# LCD.net
KiCad netlist of a schematic drawn in Altium Designer
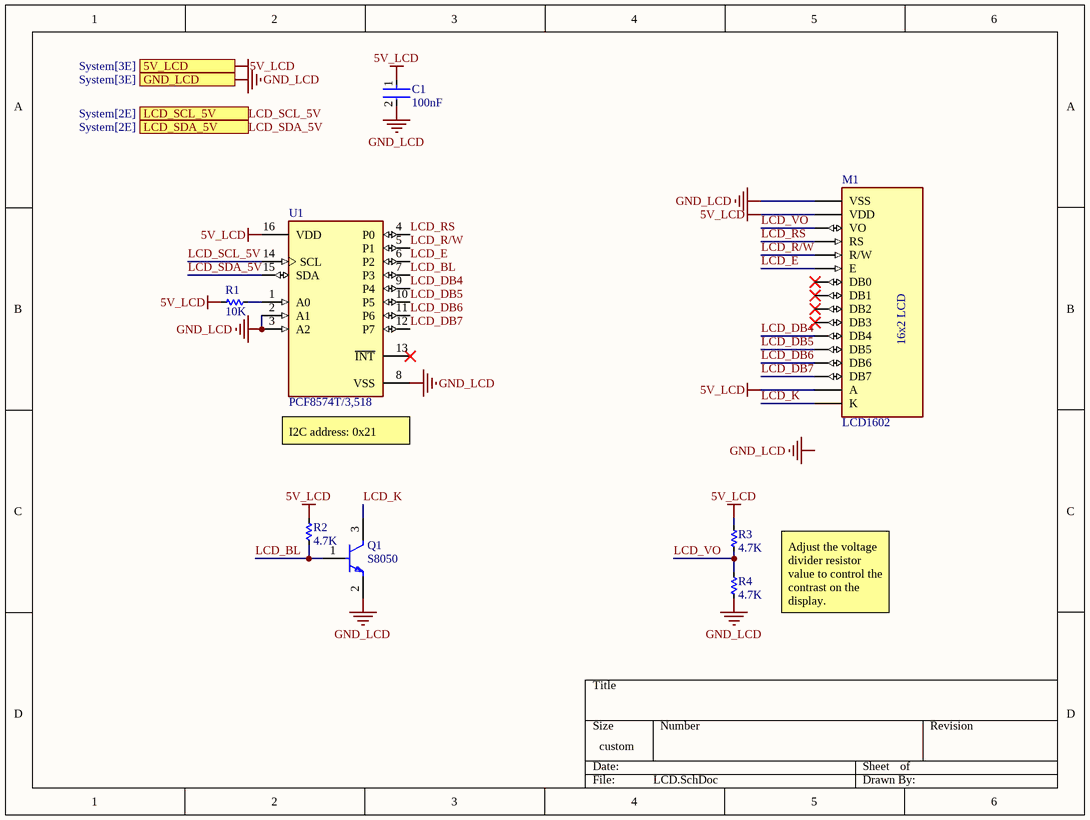
[diagram p0: LCD.SchDoc]

(export (version "E")
  (design (tool "Eeschema 10.0.6"))
  (components
    (comp (ref "C1")
      (value "100nF")
      (footprint "FP-GRM18-0_15-MFG")
      (description "CAP CER 104 0603")
      (fields
        (field (name "OCTOPART") "https://octopart.com/grm188r61a106ke69d-murata-22851381")
        (field (name "MANUFACTURER PART NUMBER") "GRM188R61A106KE69D")
      )
      (libsource (lib "Altium Content Vault") (part "11868f565c42a9108669ba33697ecf6"))
    )
    (comp (ref "M1") (value "LCD1602") (footprint "LCD1602'") (libsource (lib "Schlib1") (part "LCD1602")))
    (comp (ref "Q1")
      (value "S8050")
      (footprint "FP-SS8050-G-IPC_A")
      (description "S8050 J3Y MBT8050LT1G NPN Transistor 0.5A 40V SOT-23")
      (libsource (lib "Altium Content Vault") (part "2a1388f82443b098dcd57d24ac7632d"))
    )
    (comp (ref "R1")
      (value "10K")
      (footprint "RES-SMD-0603")
      (description "Res 0603 5%")
      (fields
        (field (name "MANUFACTURER") "Generic Components")
        (field (name "PUBLISHER") "Altium Hobart Technology Centre")
      )
      (libsource (lib "TechMT.VN_Lib_Project v2") (part "Res-SMD"))
    )
    (comp (ref "R2")
      (value "4.7K")
      (footprint "RES-SMD-0603")
      (description "Res 0603 5%")
      (fields
        (field (name "MANUFACTURER") "Generic Components")
        (field (name "PUBLISHER") "Altium Hobart Technology Centre")
      )
      (libsource (lib "TechMT.VN_Lib_Project v2") (part "Res-SMD"))
    )
    (comp (ref "R3")
      (value "4.7K")
      (footprint "RES-SMD-0603")
      (description "Res 0603 5%")
      (fields
        (field (name "MANUFACTURER") "Generic Components")
        (field (name "PUBLISHER") "Altium Hobart Technology Centre")
      )
      (libsource (lib "TechMT.VN_Lib_Project v2") (part "Res-SMD"))
    )
    (comp (ref "R4")
      (value "4.7K")
      (footprint "RES-SMD-0603")
      (description "Res 0603 5%")
      (fields
        (field (name "MANUFACTURER") "Generic Components")
        (field (name "PUBLISHER") "Altium Hobart Technology Centre")
      )
      (libsource (lib "TechMT.VN_Lib_Project v2") (part "Res-SMD"))
    )
    (comp (ref "U1")
      (value "PCF8574T/3,518")
      (footprint "FP-SOT162-1-IPC_B")
      (description "IC I/O EXPANDER I2C 8B 16SOIC")
      (fields
        (field (name "MANUFACTURER") "NXP Semiconductors")
        (field (name "OCTOPART") "https://octopart.com/pcf8574t%2F3%2C518-nxp+semiconductors-10470852")
      )
      (libsource (lib "Altium Content Vault") (part "f7fde53ce59de981fb0b266a4e103eb"))
    )
  )
  (nets
    (net (code "1") (name "/LCD_BL") (class "Default")
      (node (ref "Q1") (pin "1") (pinfunction "B_1") (pintype "passive"))
      (node (ref "R2") (pin "2") (pinfunction "2_2") (pintype "passive"))
      (node (ref "U1") (pin "7") (pinfunction "P3_7") (pintype "bidirectional"))
    )
    (net (code "2") (name "/LCD_DB4") (class "Default")
      (node (ref "M1") (pin "11") (pinfunction "DB4_11") (pintype "bidirectional"))
      (node (ref "U1") (pin "9") (pinfunction "P4_9") (pintype "bidirectional"))
    )
    (net (code "3") (name "/LCD_DB5") (class "Default")
      (node (ref "M1") (pin "12") (pinfunction "DB5_12") (pintype "bidirectional"))
      (node (ref "U1") (pin "10") (pinfunction "P5_10") (pintype "bidirectional"))
    )
    (net (code "4") (name "/LCD_DB6") (class "Default")
      (node (ref "M1") (pin "13") (pinfunction "DB6_13") (pintype "bidirectional"))
      (node (ref "U1") (pin "11") (pinfunction "P6_11") (pintype "bidirectional"))
    )
    (net (code "5") (name "/LCD_DB7") (class "Default")
      (node (ref "M1") (pin "14") (pinfunction "DB7_14") (pintype "bidirectional"))
      (node (ref "U1") (pin "12") (pinfunction "P7_12") (pintype "bidirectional"))
    )
    (net (code "6") (name "/LCD_E") (class "Default")
      (node (ref "M1") (pin "6") (pinfunction "E_6") (pintype "input"))
      (node (ref "U1") (pin "6") (pinfunction "P2_6") (pintype "bidirectional"))
    )
    (net (code "7") (name "/LCD_K") (class "Default")
      (node (ref "M1") (pin "16") (pinfunction "K_16") (pintype "power_in"))
      (node (ref "Q1") (pin "3") (pinfunction "C_3") (pintype "passive"))
    )
    (net (code "8") (name "/LCD_RS") (class "Default")
      (node (ref "M1") (pin "4") (pinfunction "RS_4") (pintype "input"))
      (node (ref "U1") (pin "4") (pinfunction "P0_4") (pintype "bidirectional"))
    )
    (net (code "9") (name "/LCD_R{slash}W") (class "Default")
      (node (ref "M1") (pin "5") (pinfunction "R/W_5") (pintype "input"))
      (node (ref "U1") (pin "5") (pinfunction "P1_5") (pintype "bidirectional"))
    )
    (net (code "10") (name "/LCD_SCL_5V") (class "Default")
      (node (ref "U1") (pin "14") (pinfunction "SCL_14") (pintype "input"))
    )
    (net (code "11") (name "/LCD_SDA_5V") (class "Default")
      (node (ref "U1") (pin "15") (pinfunction "SDA_15") (pintype "bidirectional"))
    )
    (net (code "12") (name "/LCD_VO") (class "Default")
      (node (ref "M1") (pin "3") (pinfunction "VO_3") (pintype "bidirectional"))
      (node (ref "R3") (pin "2") (pinfunction "2_2") (pintype "passive"))
      (node (ref "R4") (pin "1") (pinfunction "1_1") (pintype "passive"))
    )
    (net (code "13") (name "5V_LCD") (class "Default")
      (node (ref "C1") (pin "1") (pinfunction "1_1") (pintype "passive"))
      (node (ref "M1") (pin "15") (pinfunction "A_15") (pintype "power_in"))
      (node (ref "M1") (pin "2") (pinfunction "VDD_2") (pintype "power_in"))
      (node (ref "R1") (pin "2") (pinfunction "2_2") (pintype "passive"))
      (node (ref "R2") (pin "1") (pinfunction "1_1") (pintype "passive"))
      (node (ref "R3") (pin "1") (pinfunction "1_1") (pintype "passive"))
      (node (ref "U1") (pin "16") (pinfunction "VDD_16") (pintype "power_in"))
    )
    (net (code "14") (name "GND_LCD") (class "Default")
      (node (ref "C1") (pin "2") (pinfunction "2_2") (pintype "passive"))
      (node (ref "M1") (pin "1") (pinfunction "VSS_1") (pintype "power_in"))
      (node (ref "Q1") (pin "2") (pinfunction "E_2") (pintype "passive"))
      (node (ref "R4") (pin "2") (pinfunction "2_2") (pintype "passive"))
      (node (ref "U1") (pin "2") (pinfunction "A1_2") (pintype "input"))
      (node (ref "U1") (pin "3") (pinfunction "A2_3") (pintype "input"))
      (node (ref "U1") (pin "8") (pinfunction "VSS_8") (pintype "power_in"))
    )
    (net (code "15") (name "Net-(U1-A0)") (class "Default")
      (node (ref "R1") (pin "1") (pinfunction "1_1") (pintype "passive"))
      (node (ref "U1") (pin "1") (pinfunction "A0_1") (pintype "input"))
    )
    (net (code "16") (name "unconnected-(M1-DB0-Pad7)") (class "Default")
      (node (ref "M1") (pin "7") (pinfunction "DB0_7") (pintype "bidirectional+no_connect"))
    )
    (net (code "17") (name "unconnected-(M1-DB1-Pad8)") (class "Default")
      (node (ref "M1") (pin "8") (pinfunction "DB1_8") (pintype "bidirectional+no_connect"))
    )
    (net (code "18") (name "unconnected-(M1-DB2-Pad9)") (class "Default")
      (node (ref "M1") (pin "9") (pinfunction "DB2_9") (pintype "bidirectional+no_connect"))
    )
    (net (code "19") (name "unconnected-(M1-DB3-Pad10)") (class "Default")
      (node (ref "M1") (pin "10") (pinfunction "DB3_10") (pintype "bidirectional+no_connect"))
    )
    (net (code "20") (name "unconnected-(U1-~{INT}-Pad13)") (class "Default")
      (node (ref "U1") (pin "13") (pinfunction "~{INT}_13") (pintype "open_collector+no_connect"))
    )
  )
)
